# OSO-TIBO-A1-01.net
KiCad netlist of a schematic drawn in EAGLE
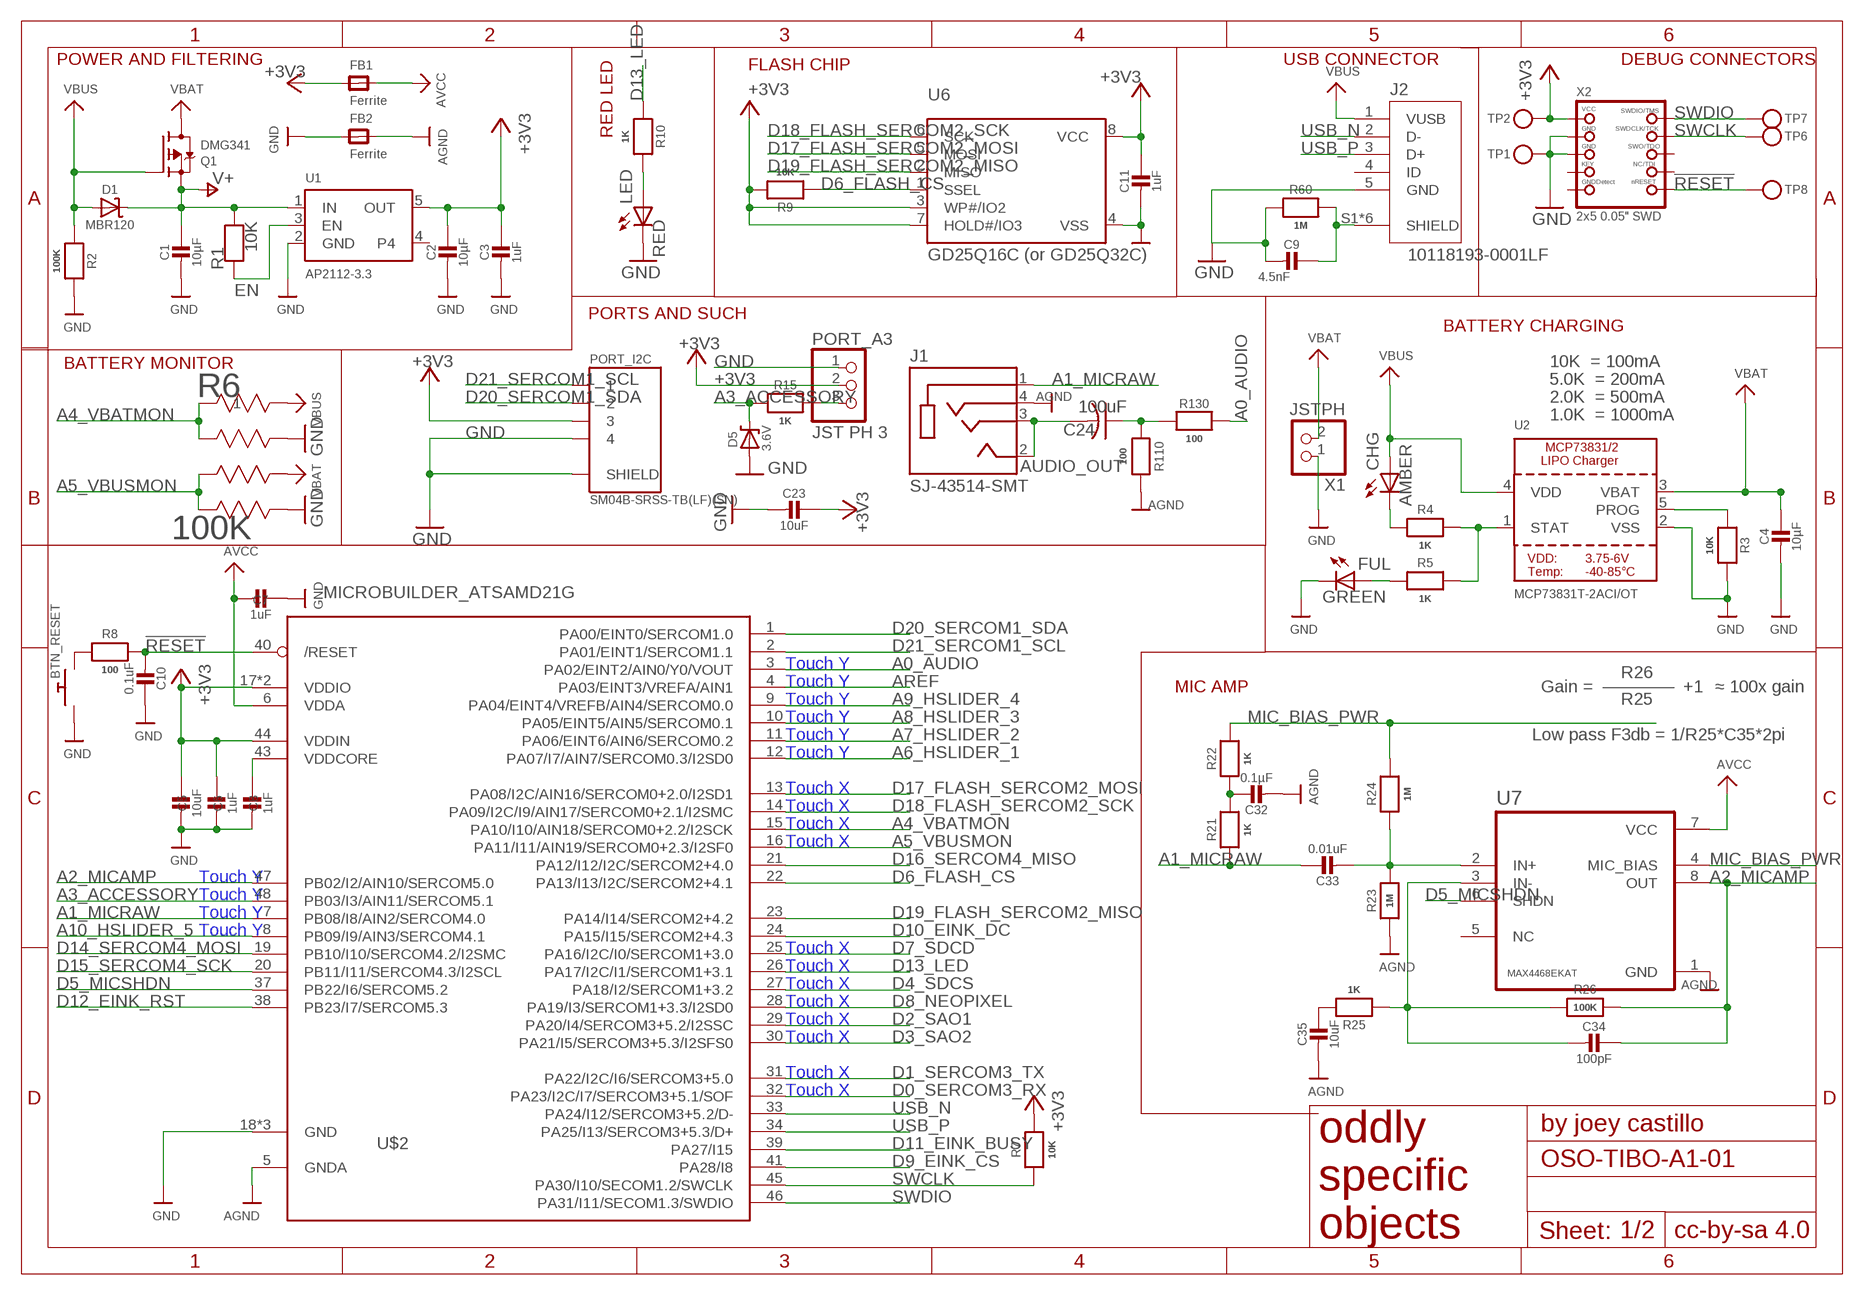
[diagram p0: schematic, sheet 1]
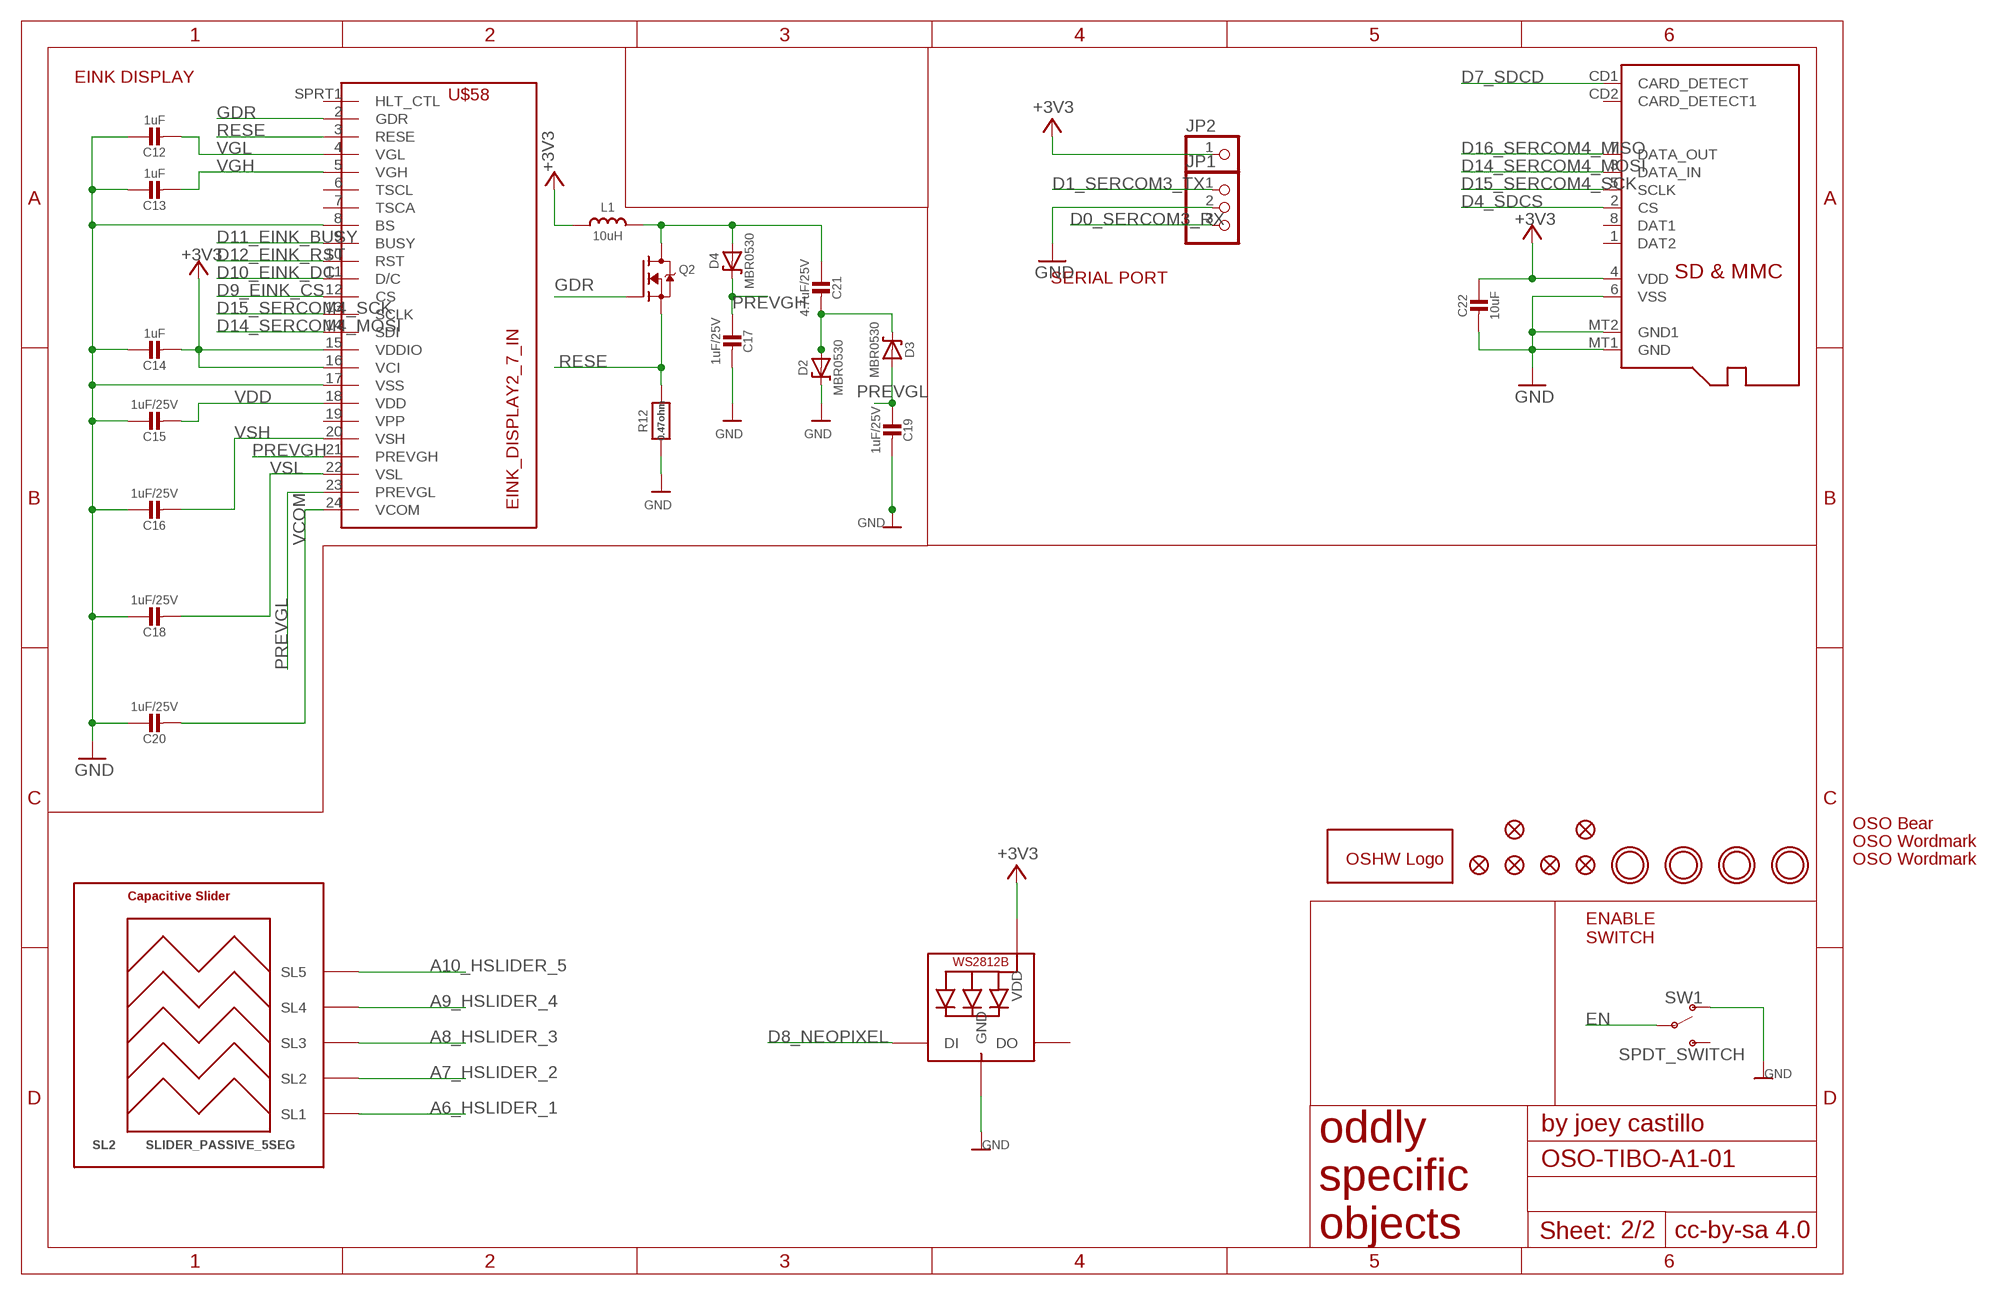
[diagram p1: schematic, sheet 2]

(export (version "E")
  (design (tool "Eeschema 10.0.6"))
  (components
    (comp (ref "BTN_RESET")
      (value "SPST_TACTILE_SWITCHRA-THRU")
      (footprint "eagle-import:MJTP1117")
      (libsource (lib "eagle-import") (part "SPST_TACTILE_SWITCHRA-THRU"))
    )
    (comp (ref "C1")
      (value "10µF")
      (footprint "eagle-import:0805-NO")
      (libsource (lib "eagle-import") (part "CAP_CERAMIC0805-NOOUTLINE"))
    )
    (comp (ref "C2")
      (value "10µF")
      (footprint "eagle-import:0805-NO")
      (libsource (lib "eagle-import") (part "CAP_CERAMIC0805-NOOUTLINE"))
    )
    (comp (ref "C3")
      (value "1uF")
      (footprint "eagle-import:0805-NO")
      (libsource (lib "eagle-import") (part "CAP_CERAMIC0805-NOOUTLINE"))
    )
    (comp (ref "C4")
      (value "10µF")
      (footprint "eagle-import:0805-NO")
      (libsource (lib "eagle-import") (part "CAP_CERAMIC0805-NOOUTLINE"))
    )
    (comp (ref "C5")
      (value "10uF")
      (footprint "eagle-import:0805_10MGAP")
      (libsource (lib "eagle-import") (part "CAP_CERAMIC0805_10MGAP"))
    )
    (comp (ref "C6")
      (value "1uF")
      (footprint "eagle-import:0805-NO")
      (libsource (lib "eagle-import") (part "CAP_CERAMIC0805-NOOUTLINE"))
    )
    (comp (ref "C7")
      (value "1uF")
      (footprint "eagle-import:0805-NO")
      (libsource (lib "eagle-import") (part "CAP_CERAMIC0805-NOOUTLINE"))
    )
    (comp (ref "C8")
      (value "1uF")
      (footprint "eagle-import:0805-NO")
      (libsource (lib "eagle-import") (part "CAP_CERAMIC0805-NOOUTLINE"))
    )
    (comp (ref "C9")
      (value "4.5nF")
      (footprint "eagle-import:0805-NO")
      (libsource (lib "eagle-import") (part "CAP_CERAMIC0805-NOOUTLINE"))
    )
    (comp (ref "C10")
      (value "0.1uF")
      (footprint "eagle-import:0805_10MGAP")
      (libsource (lib "eagle-import") (part "CAP_CERAMIC0805_10MGAP"))
    )
    (comp (ref "C11")
      (value "1uF")
      (footprint "eagle-import:0805_10MGAP")
      (libsource (lib "eagle-import") (part "CAP_CERAMIC0805_10MGAP"))
    )
    (comp (ref "C23")
      (value "10uF")
      (footprint "eagle-import:0805-NO")
      (libsource (lib "eagle-import") (part "CAP_CERAMIC0805-NOOUTLINE"))
    )
    (comp (ref "C24")
      (value "100uF")
      (footprint "eagle-import:C1210")
      (libsource (lib "eagle-import") (part "C-USC1210"))
    )
    (comp (ref "C32")
      (value "0.1µF")
      (footprint "eagle-import:0805-NO")
      (libsource (lib "eagle-import") (part "CAP_CERAMIC0805-NOOUTLINE"))
    )
    (comp (ref "C33")
      (value "0.01uF")
      (footprint "eagle-import:0805-NO")
      (libsource (lib "eagle-import") (part "CAP_CERAMIC0805-NOOUTLINE"))
    )
    (comp (ref "C34")
      (value "100pF")
      (footprint "eagle-import:0805-NO")
      (libsource (lib "eagle-import") (part "CAP_CERAMIC0805-NOOUTLINE"))
    )
    (comp (ref "C35")
      (value "10uF")
      (footprint "eagle-import:0805-NO")
      (libsource (lib "eagle-import") (part "CAP_CERAMIC0805-NOOUTLINE"))
    )
    (comp (ref "CHG")
      (value "AMBER")
      (footprint "eagle-import:CHIP-LED0805")
      (libsource (lib "eagle-import") (part "LEDCHIP-LED0805"))
    )
    (comp (ref "D1")
      (value "MBR120")
      (footprint "eagle-import:SOD-123")
      (libsource (lib "eagle-import") (part "DIODE-SCHOTTKYSOD-123"))
    )
    (comp (ref "D5")
      (value "3.6V")
      (footprint "eagle-import:SOD-123")
      (libsource (lib "eagle-import") (part "DIODE-ZENERSOD123"))
    )
    (comp (ref "FB1")
      (value "Ferrite")
      (footprint "eagle-import:0805")
      (libsource (lib "eagle-import") (part "FERRITE0805"))
    )
    (comp (ref "FB2")
      (value "Ferrite")
      (footprint "eagle-import:0805")
      (libsource (lib "eagle-import") (part "FERRITE0805"))
    )
    (comp (ref "FUL")
      (value "GREEN")
      (footprint "eagle-import:CHIP-LED0805")
      (libsource (lib "eagle-import") (part "LEDCHIP-LED0805"))
    )
    (comp (ref "J1")
      (value "SJ-43514-SMT")
      (footprint "eagle-import:CUI_SJ-43514-SMT")
      (fields
        (field (name "DIGI-KEY_PART_NUMBER") "CP-43514SJCT-ND")
        (field (name "MF") "CUI Inc.")
        (field (name "MP") "SJ-43514-SMT-TR")
      )
      (libsource (lib "eagle-import") (part "SJ-43514-SMT"))
    )
    (comp (ref "J2")
      (value "10118193-0001LF")
      (footprint "eagle-import:FCI_10118193-0001LF")
      (fields (field (name "DIGI-KEY_PART_NUMBER") "609-4616-1-ND") (field (name "MF") "Amphenol ICC"))
      (libsource (lib "eagle-import") (part "10118193-0001LF"))
    )
    (comp (ref "LED")
      (value "RED")
      (footprint "eagle-import:CHIP-LED0805")
      (libsource (lib "eagle-import") (part "LEDCHIP-LED0805"))
    )
    (comp (ref "PORT_A3")
      (value "JST PH 3")
      (footprint "eagle-import:JSTPH3")
      (libsource (lib "eagle-import") (part "CON_JST_PH_3PIN"))
    )
    (comp (ref "PORT_I2C")
      (value "SM04B-SRSS-TB(LF)(SN)")
      (footprint "eagle-import:JST_SM04B-SRSS-TB(LF)(SN)")
      (fields
        (field (name "DIGI-KEY_PART_NUMBER") "455-1804-1-ND")
        (field (name "MF") "JST Sales")
        (field (name "MP") "SM04B-SRSS-TB_LF__SN_")
      )
      (libsource (lib "eagle-import") (part "SM04B-SRSS-TB(LF)(SN)"))
    )
    (comp (ref "Q1")
      (value "DMG341")
      (footprint "eagle-import:SOT23-R")
      (libsource (lib "eagle-import") (part "MOSFET-P"))
    )
    (comp (ref "R1")
      (value "10K")
      (footprint "eagle-import:0805-NO")
      (libsource (lib "eagle-import") (part "RESISTOR0805_NOOUTLINE"))
    )
    (comp (ref "R2")
      (value "100K")
      (footprint "eagle-import:0805-NO")
      (libsource (lib "eagle-import") (part "RESISTOR0805_NOOUTLINE"))
    )
    (comp (ref "R3")
      (value "10K")
      (footprint "eagle-import:0805-NO")
      (libsource (lib "eagle-import") (part "RESISTOR0805_NOOUTLINE"))
    )
    (comp (ref "R4")
      (value "1K")
      (footprint "eagle-import:0805-NO")
      (libsource (lib "eagle-import") (part "RESISTOR0805_NOOUTLINE"))
    )
    (comp (ref "R5")
      (value "1K")
      (footprint "eagle-import:0805-NO")
      (libsource (lib "eagle-import") (part "RESISTOR0805_NOOUTLINE"))
    )
    (comp (ref "R6")
      (value "100K")
      (footprint "eagle-import:EXBV8V")
      (fields (field (name "MANUFACTURER_PART_NUMBER") "EXBV8V103JV"))
      (libsource (lib "eagle-import") (part "EXB-V8V103JV"))
    )
    (comp (ref "R7")
      (value "10K")
      (footprint "eagle-import:0805-NO")
      (libsource (lib "eagle-import") (part "RESISTOR0805_NOOUTLINE"))
    )
    (comp (ref "R8")
      (value "100")
      (footprint "eagle-import:0805_10MGAP")
      (libsource (lib "eagle-import") (part "RESISTOR0805_10MGAP"))
    )
    (comp (ref "R9")
      (value "10K")
      (footprint "eagle-import:0805-NO")
      (libsource (lib "eagle-import") (part "RESISTOR0805_NOOUTLINE"))
    )
    (comp (ref "R10")
      (value "1K")
      (footprint "eagle-import:0805-NO")
      (libsource (lib "eagle-import") (part "RESISTOR0805_NOOUTLINE"))
    )
    (comp (ref "R15")
      (value "1K")
      (footprint "eagle-import:_0805MP")
      (libsource (lib "eagle-import") (part "RESISTOR_0805MP"))
    )
    (comp (ref "R21")
      (value "1K")
      (footprint "eagle-import:0805-NO")
      (libsource (lib "eagle-import") (part "RESISTOR0805_NOOUTLINE"))
    )
    (comp (ref "R22")
      (value "1K")
      (footprint "eagle-import:0805-NO")
      (libsource (lib "eagle-import") (part "RESISTOR0805_NOOUTLINE"))
    )
    (comp (ref "R23")
      (value "1M")
      (footprint "eagle-import:0805-NO")
      (libsource (lib "eagle-import") (part "RESISTOR0805_NOOUTLINE"))
    )
    (comp (ref "R24")
      (value "1M")
      (footprint "eagle-import:0805-NO")
      (libsource (lib "eagle-import") (part "RESISTOR0805_NOOUTLINE"))
    )
    (comp (ref "R25")
      (value "1K")
      (footprint "eagle-import:0805-NO")
      (libsource (lib "eagle-import") (part "RESISTOR0805_NOOUTLINE"))
    )
    (comp (ref "R26")
      (value "100K")
      (footprint "eagle-import:0805-NO")
      (libsource (lib "eagle-import") (part "RESISTOR0805_NOOUTLINE"))
    )
    (comp (ref "R60")
      (value "1M")
      (footprint "eagle-import:0805-NO")
      (libsource (lib "eagle-import") (part "RESISTOR0805_NOOUTLINE"))
    )
    (comp (ref "R110")
      (value "100")
      (footprint "eagle-import:0805-NO")
      (libsource (lib "eagle-import") (part "RESISTOR0805_NOOUTLINE"))
    )
    (comp (ref "R130")
      (value "100")
      (footprint "eagle-import:0805-NO")
      (libsource (lib "eagle-import") (part "RESISTOR0805_NOOUTLINE"))
    )
    (comp (ref "TP1")
      (value "TESTPOINTROUND2MMNO")
      (footprint "eagle-import:TESTPOINT_ROUND_2MM_NO")
      (libsource (lib "eagle-import") (part "TESTPOINTROUND2MMNO"))
    )
    (comp (ref "TP2")
      (value "TESTPOINTROUND2MMNO")
      (footprint "eagle-import:TESTPOINT_ROUND_2MM_NO")
      (libsource (lib "eagle-import") (part "TESTPOINTROUND2MMNO"))
    )
    (comp (ref "TP6")
      (value "TESTPOINTROUND2MMNO")
      (footprint "eagle-import:TESTPOINT_ROUND_2MM_NO")
      (libsource (lib "eagle-import") (part "TESTPOINTROUND2MMNO"))
    )
    (comp (ref "TP7")
      (value "TESTPOINTROUND2MMNO")
      (footprint "eagle-import:TESTPOINT_ROUND_2MM_NO")
      (libsource (lib "eagle-import") (part "TESTPOINTROUND2MMNO"))
    )
    (comp (ref "TP8")
      (value "TESTPOINTROUND2MMNO")
      (footprint "eagle-import:TESTPOINT_ROUND_2MM_NO")
      (libsource (lib "eagle-import") (part "TESTPOINTROUND2MMNO"))
    )
    (comp (ref "U$2")
      (value "MICROBUILDER_ATSAMD21G")
      (footprint "eagle-import:QFP50P900X900X120-48N")
      (libsource (lib "eagle-import") (part "MICROBUILDER_ATSAMD21G"))
    )
    (comp (ref "U1")
      (value "AP2112-3.3")
      (footprint "eagle-import:SOT23-5")
      (libsource (lib "eagle-import") (part "VREG_SOT23-5"))
    )
    (comp (ref "U2")
      (value "MCP73831T-2ACI/OT")
      (footprint "eagle-import:SOT23-5")
      (libsource (lib "eagle-import") (part "MCP73831/2"))
    )
    (comp (ref "U6")
      (value "GD25Q16C (or GD25Q32C)")
      (footprint "eagle-import:MICROBUILDER_SOIC8_150MIL")
      (libsource (lib "eagle-import") (part "MICROBUILDER_SPIFLASH_SOIC8"))
    )
    (comp (ref "U7")
      (value "MAX4468EKAT")
      (footprint "eagle-import:SOT65P280X145-8N")
      (fields
        (field (name "DIGI-KEY_PART_NUMBER") "MAX4468EKA+CT-ND")
        (field (name "MF") "Maxim Integrated")
        (field (name "MP") "MAX4468EKA+T")
      )
      (libsource (lib "eagle-import") (part "MAX4468EKAT"))
    )
    (comp (ref "X1")
      (value "JSTPH")
      (footprint "eagle-import:JSTPH2")
      (libsource (lib "eagle-import") (part "CON_JST_PH_2PIN"))
    )
    (comp (ref "X2")
      (value "2x5 0.05\" SWD")
      (footprint "eagle-import:2X05_1.27MM_BOX_POSTS")
      (libsource (lib "eagle-import") (part "JTAG-CORTEXBOXPOSTS"))
    )
    (comp (ref "C12")
      (value "1uF")
      (footprint "eagle-import:0805_10MGAP")
      (libsource (lib "eagle-import") (part "CAP_CERAMIC0805_10MGAP"))
    )
    (comp (ref "C13")
      (value "1uF")
      (footprint "eagle-import:0805_10MGAP")
      (libsource (lib "eagle-import") (part "CAP_CERAMIC0805_10MGAP"))
    )
    (comp (ref "C14")
      (value "1uF")
      (footprint "eagle-import:0805_10MGAP")
      (libsource (lib "eagle-import") (part "CAP_CERAMIC0805_10MGAP"))
    )
    (comp (ref "C15")
      (value "1uF/25V")
      (footprint "eagle-import:0805_10MGAP")
      (libsource (lib "eagle-import") (part "CAP_CERAMIC0805_10MGAP"))
    )
    (comp (ref "C16")
      (value "1uF/25V")
      (footprint "eagle-import:0805_10MGAP")
      (libsource (lib "eagle-import") (part "CAP_CERAMIC0805_10MGAP"))
    )
    (comp (ref "C17")
      (value "1uF/25V")
      (footprint "eagle-import:0805_10MGAP")
      (libsource (lib "eagle-import") (part "CAP_CERAMIC0805_10MGAP"))
    )
    (comp (ref "C18")
      (value "1uF/25V")
      (footprint "eagle-import:0805_10MGAP")
      (libsource (lib "eagle-import") (part "CAP_CERAMIC0805_10MGAP"))
    )
    (comp (ref "C19")
      (value "1uF/25V")
      (footprint "eagle-import:0805_10MGAP")
      (libsource (lib "eagle-import") (part "CAP_CERAMIC0805_10MGAP"))
    )
    (comp (ref "C20")
      (value "1uF/25V")
      (footprint "eagle-import:0805_10MGAP")
      (libsource (lib "eagle-import") (part "CAP_CERAMIC0805_10MGAP"))
    )
    (comp (ref "C21")
      (value "4.7uF/25V")
      (footprint "eagle-import:0805-NO")
      (libsource (lib "eagle-import") (part "CAP_CERAMIC0805-NOOUTLINE"))
    )
    (comp (ref "C22")
      (value "10uF")
      (footprint "eagle-import:0805_10MGAP")
      (libsource (lib "eagle-import") (part "CAP_CERAMIC0805_10MGAP"))
    )
    (comp (ref "D2")
      (value "MBR0530")
      (footprint "eagle-import:SOD-123")
      (libsource (lib "eagle-import") (part "DIODE-SCHOTTKYSOD-123"))
    )
    (comp (ref "D3")
      (value "MBR0530")
      (footprint "eagle-import:SOD-123")
      (libsource (lib "eagle-import") (part "DIODE-SCHOTTKYSOD-123"))
    )
    (comp (ref "D4")
      (value "MBR0530")
      (footprint "eagle-import:SOD-123")
      (libsource (lib "eagle-import") (part "DIODE-SCHOTTKYSOD-123"))
    )
    (comp (ref "D8_NEOPIXEL")
      (value "WS2812B_4020")
      (footprint "eagle-import:WS2812B_4020")
      (libsource (lib "eagle-import") (part "WS2812B_4020"))
    )
    (comp (ref "FID1")
      (value "FIDUCIAL_1MM")
      (footprint "eagle-import:FIDUCIAL_1MM")
      (libsource (lib "eagle-import") (part "FIDUCIAL_1MM"))
    )
    (comp (ref "FID2")
      (value "FIDUCIAL_1MM")
      (footprint "eagle-import:FIDUCIAL_1MM")
      (libsource (lib "eagle-import") (part "FIDUCIAL_1MM"))
    )
    (comp (ref "FID3")
      (value "FIDUCIAL_1MM")
      (footprint "eagle-import:FIDUCIAL_1MM")
      (libsource (lib "eagle-import") (part "FIDUCIAL_1MM"))
    )
    (comp (ref "FID4")
      (value "FIDUCIAL_1MM")
      (footprint "eagle-import:FIDUCIAL_1MM")
      (libsource (lib "eagle-import") (part "FIDUCIAL_1MM"))
    )
    (comp (ref "FID5")
      (value "FIDUCIAL_1MM")
      (footprint "eagle-import:FIDUCIAL_1MM")
      (libsource (lib "eagle-import") (part "FIDUCIAL_1MM"))
    )
    (comp (ref "FID6")
      (value "FIDUCIAL_1MM")
      (footprint "eagle-import:FIDUCIAL_1MM")
      (libsource (lib "eagle-import") (part "FIDUCIAL_1MM"))
    )
    (comp (ref "GOLD_ORB_SM1")
      (value "OSHWLOGOLOGO5MM")
      (footprint "eagle-import:OSHW_5MM")
      (libsource (lib "eagle-import") (part "OSHWLOGOLOGO5MM"))
    )
    (comp (ref "JP1")
      (value "PINHD-1X3")
      (footprint "eagle-import:1X03")
      (libsource (lib "eagle-import") (part "PINHD-1X3"))
    )
    (comp (ref "JP2")
      (value "PINHD-1X1")
      (footprint "eagle-import:1X01")
      (libsource (lib "eagle-import") (part "PINHD-1X1"))
    )
    (comp (ref "L1")
      (value "10uH")
      (footprint "eagle-import:INDUCTOR_4X4MM_NR401")
      (libsource (lib "eagle-import") (part "INDUCTORNR401"))
    )
    (comp (ref "MICROSD")
      (value "MICROSD")
      (footprint "eagle-import:MICROSD")
      (libsource (lib "eagle-import") (part "MICROSD"))
    )
    (comp (ref "Q2")
      (value "IRLML0100")
      (footprint "eagle-import:SOT23-3")
      (libsource (lib "eagle-import") (part "IRLML2060TRPBF"))
    )
    (comp (ref "R12")
      (value "0.47ohm")
      (footprint "eagle-import:0805_10MGAP")
      (libsource (lib "eagle-import") (part "RESISTOR0805_10MGAP"))
    )
    (comp (ref "SL2")
      (value "SLIDER_PASSIVE_5SEG")
      (footprint "eagle-import:SLIDER_PASSIVE_5SEG_12MM")
      (libsource (lib "eagle-import") (part "SLIDER_PASSIVE_5SEG"))
    )
    (comp (ref "SW1")
      (value "SPDT_SWITCH")
      (footprint "eagle-import:A10767")
      (libsource (lib "eagle-import") (part "SPDT_SWITCH"))
    )
    (comp (ref "U$1")
      (value "MOUNTINGHOLE2.5")
      (footprint "eagle-import:MOUNTINGHOLE_2.5_PLATED")
      (libsource (lib "eagle-import") (part "MOUNTINGHOLE2.5"))
    )
    (comp (ref "U$4")
      (value "MOUNTINGHOLE2.5")
      (footprint "eagle-import:MOUNTINGHOLE_2.5_PLATED")
      (libsource (lib "eagle-import") (part "MOUNTINGHOLE2.5"))
    )
    (comp (ref "U$5")
      (value "MOUNTINGHOLE2.5")
      (footprint "eagle-import:MOUNTINGHOLE_2.5_PLATED")
      (libsource (lib "eagle-import") (part "MOUNTINGHOLE2.5"))
    )
    (comp (ref "U$7")
      (value "MOUNTINGHOLE2.5")
      (footprint "eagle-import:MOUNTINGHOLE_2.5_PLATED")
      (libsource (lib "eagle-import") (part "MOUNTINGHOLE2.5"))
    )
    (comp (ref "U$45")
      (value "OSO_BEAR")
      (footprint "eagle-import:OSO_BEAR_750MIL")
      (libsource (lib "eagle-import") (part "OSO_BEAR"))
    )
    (comp (ref "U$47")
      (value "OSO_TEXT")
      (footprint "eagle-import:OSO_TEXT_435MIL")
      (libsource (lib "eagle-import") (part "OSO_TEXT"))
    )
    (comp (ref "U$48")
      (value "OSO_TEXTOSO_TEXT_ONELINE_125MIL")
      (footprint "eagle-import:OSO_ONELINE_125MIL")
      (libsource (lib "eagle-import") (part "OSO_TEXTOSO_TEXT_ONELINE_125MIL"))
    )
    (comp (ref "U$58")
      (value "EINK_DISPLAY2_7_IN")
      (footprint "eagle-import:EINK_DISPLAY_2_7_IN")
      (libsource (lib "eagle-import") (part "EINK_DISPLAY2_7_IN"))
    )
  )
  (nets
    (net (code "1") (name "+3V3") (class "Default")
      (node (ref "C11") (pin "1") (pinfunction "1_1") (pintype "passive"))
      (node (ref "C14") (pin "2") (pinfunction "2_2") (pintype "passive"))
      (node (ref "C2") (pin "1") (pinfunction "1_1") (pintype "passive"))
      (node (ref "C22") (pin "1") (pinfunction "1_1") (pintype "passive"))
      (node (ref "C23") (pin "1") (pinfunction "1_1") (pintype "passive"))
      (node (ref "C3") (pin "1") (pinfunction "1_1") (pintype "passive"))
      (node (ref "C5") (pin "1") (pinfunction "1_1") (pintype "passive"))
      (node (ref "C6") (pin "1") (pinfunction "1_1") (pintype "passive"))
      (node (ref "D8_NEOPIXEL") (pin "2") (pinfunction "VDD_2") (pintype "power_in"))
      (node (ref "FB1") (pin "1") (pinfunction "P$1_1") (pintype "passive"))
      (node (ref "JP2") (pin "1") (pinfunction "1_1") (pintype "passive"))
      (node (ref "L1") (pin "P$2") (pinfunction "2_P$2") (pintype "passive"))
      (node (ref "MICROSD") (pin "4") (pinfunction "VDD_4") (pintype "power_in"))
      (node (ref "PORT_A3") (pin "2") (pinfunction "2_2") (pintype "passive"))
      (node (ref "PORT_I2C") (pin "3") (pinfunction "3_3") (pintype "passive"))
      (node (ref "R7") (pin "2") (pinfunction "2_2") (pintype "passive"))
      (node (ref "R9") (pin "2") (pinfunction "2_2") (pintype "passive"))
      (node (ref "TP2") (pin "P$1") (pinfunction "P$1_P$1") (pintype "bidirectional"))
      (node (ref "U$2") (pin "17") (pinfunction "VDDIO_17") (pintype "power_in"))
      (node (ref "U$2") (pin "36") (pinfunction "VDDIO_36") (pintype "power_in"))
      (node (ref "U$2") (pin "44") (pinfunction "VDDIN_44") (pintype "power_in"))
      (node (ref "U$58") (pin "15") (pinfunction "VDDIO_15") (pintype "bidirectional"))
      (node (ref "U$58") (pin "16") (pinfunction "VCI_16") (pintype "bidirectional"))
      (node (ref "U1") (pin "5") (pinfunction "OUT_5") (pintype "power_in"))
      (node (ref "U6") (pin "3") (pinfunction "WP#/IO2_3") (pintype "bidirectional"))
      (node (ref "U6") (pin "7") (pinfunction "HOLD#/IO3_7") (pintype "bidirectional"))
      (node (ref "U6") (pin "8") (pinfunction "VCC_8") (pintype "bidirectional"))
      (node (ref "X2") (pin "1") (pinfunction "VCC_1") (pintype "power_in"))
    )
    (net (code "2") (name "A0_AUDIO") (class "Default")
      (node (ref "R130") (pin "1") (pinfunction "1_1") (pintype "passive"))
      (node (ref "U$2") (pin "3") (pinfunction "PA02/EINT2/AIN0/Y0/VOUT_3") (pintype "bidirectional"))
    )
    (net (code "3") (name "A1_MICRAW") (class "Default")
      (node (ref "C33") (pin "1") (pinfunction "1_1") (pintype "passive"))
      (node (ref "J1") (pin "1") (pinfunction "SLEEVE_1") (pintype "passive"))
      (node (ref "R21") (pin "1") (pinfunction "1_1") (pintype "passive"))
      (node (ref "U$2") (pin "7") (pinfunction "PB08/I8/AIN2/SERCOM4.0_7") (pintype "bidirectional"))
    )
    (net (code "4") (name "A2_MICAMP") (class "Default")
      (node (ref "C34") (pin "1") (pinfunction "1_1") (pintype "passive"))
      (node (ref "R26") (pin "2") (pinfunction "2_2") (pintype "passive"))
      (node (ref "U$2") (pin "47") (pinfunction "PB02/I2/AIN10/SERCOM5.0_47") (pintype "bidirectional"))
      (node (ref "U7") (pin "8") (pinfunction "OUT_8") (pintype "output"))
    )
    (net (code "5") (name "A3_ACCESSORY") (class "Default")
      (node (ref "D5") (pin "C") (pinfunction "C_C") (pintype "passive"))
      (node (ref "R15") (pin "2") (pinfunction "2_2") (pintype "passive"))
      (node (ref "U$2") (pin "48") (pinfunction "PB03/I3/AIN11/SERCOM5.1_48") (pintype "bidirectional"))
    )
    (net (code "6") (name "A4_VBATMON") (class "Default")
      (node (ref "R6") (pin "1") (pinfunction "1_1") (pintype "passive"))
      (node (ref "R6") (pin "2") (pinfunction "2_2") (pintype "passive"))
      (node (ref "U$2") (pin "15") (pinfunction "PA10/I10/AIN18/SERCOM0+2.2/I2SCK_15") (pintype "bidirectional"))
    )
    (net (code "7") (name "A5_VBUSMON") (class "Default")
      (node (ref "R6") (pin "3") (pinfunction "3_3") (pintype "passive"))
      (node (ref "R6") (pin "4") (pinfunction "4_4") (pintype "passive"))
      (node (ref "U$2") (pin "16") (pinfunction "PA11/I11/AIN19/SERCOM0+2.3/I2SF0_16") (pintype "bidirectional"))
    )
    (net (code "8") (name "A6_HSLIDER_1") (class "Default")
      (node (ref "SL2") (pin "SL1") (pinfunction "SL1_SL1") (pintype "passive"))
      (node (ref "U$2") (pin "12") (pinfunction "PA07/I7/AIN7/SERCOM0.3/I2SD0_12") (pintype "bidirectional"))
    )
    (net (code "9") (name "A7_HSLIDER_2") (class "Default")
      (node (ref "SL2") (pin "SL2") (pinfunction "SL2_SL2") (pintype "passive"))
      (node (ref "U$2") (pin "11") (pinfunction "PA06/EINT6/AIN6/SERCOM0.2_11") (pintype "bidirectional"))
    )
    (net (code "10") (name "A8_HSLIDER_3") (class "Default")
      (node (ref "SL2") (pin "SL3") (pinfunction "SL3_SL3") (pintype "passive"))
      (node (ref "U$2") (pin "10") (pinfunction "PA05/EINT5/AIN5/SERCOM0.1_10") (pintype "bidirectional"))
    )
    (net (code "11") (name "A9_HSLIDER_4") (class "Default")
      (node (ref "SL2") (pin "SL4") (pinfunction "SL4_SL4") (pintype "passive"))
      (node (ref "U$2") (pin "9") (pinfunction "PA04/EINT4/VREFB/AIN4/SERCOM0.0_9") (pintype "bidirectional"))
    )
    (net (code "12") (name "A10_HSLIDER_5") (class "Default")
      (node (ref "SL2") (pin "SL5") (pinfunction "SL5_SL5") (pintype "passive"))
      (node (ref "U$2") (pin "8") (pinfunction "PB09/I9/AIN3/SERCOM4.1_8") (pintype "bidirectional"))
    )
    (net (code "13") (name "AGND") (class "Default")
      (node (ref "C32") (pin "2") (pinfunction "2_2") (pintype "passive"))
      (node (ref "C35") (pin "2") (pinfunction "2_2") (pintype "passive"))
      (node (ref "FB2") (pin "2") (pinfunction "P$2_2") (pintype "passive"))
      (node (ref "J1") (pin "4") (pinfunction "RING2_4") (pintype "passive"))
      (node (ref "R110") (pin "1") (pinfunction "1_1") (pintype "passive"))
      (node (ref "R23") (pin "1") (pinfunction "1_1") (pintype "passive"))
      (node (ref "U$2") (pin "5") (pinfunction "GNDA_5") (pintype "power_in"))
      (node (ref "U7") (pin "1") (pinfunction "GND_1") (pintype "power_in"))
    )
    (net (code "14") (name "AREF") (class "Default")
      (node (ref "U$2") (pin "4") (pinfunction "PA03/EINT3/VREFA/AIN1_4") (pintype "bidirectional"))
    )
    (net (code "15") (name "AUDIO_OUT") (class "Default")
      (node (ref "C24") (pin "2") (pinfunction "2_2") (pintype "passive"))
      (node (ref "J1") (pin "2") (pinfunction "TIP_2") (pintype "passive"))
      (node (ref "J1") (pin "3") (pinfunction "RING1_3") (pintype "passive"))
    )
    (net (code "16") (name "AVCC") (class "Default")
      (node (ref "C7") (pin "2") (pinfunction "2_2") (pintype "passive"))
      (node (ref "FB1") (pin "2") (pinfunction "P$2_2") (pintype "passive"))
      (node (ref "U$2") (pin "6") (pinfunction "VDDA_6") (pintype "power_in"))
      (node (ref "U7") (pin "7") (pinfunction "VCC_7") (pintype "power_in"))
    )
    (net (code "17") (name "D0_SERCOM3_RX") (class "Default")
      (node (ref "JP1") (pin "3") (pinfunction "3_3") (pintype "passive"))
      (node (ref "U$2") (pin "32") (pinfunction "PA23/I2C/I7/SERCOM3+5.1/SOF_32") (pintype "bidirectional"))
    )
    (net (code "18") (name "D1_SERCOM3_TX") (class "Default")
      (node (ref "JP1") (pin "1") (pinfunction "1_1") (pintype "passive"))
      (node (ref "U$2") (pin "31") (pinfunction "PA22/I2C/I6/SERCOM3+5.0_31") (pintype "bidirectional"))
    )
    (net (code "19") (name "D2_SAO1") (class "Default")
      (node (ref "U$2") (pin "29") (pinfunction "PA20/I4/SERCOM3+5.2/I2SSC_29") (pintype "bidirectional"))
    )
    (net (code "20") (name "D3_SAO2") (class "Default")
      (node (ref "U$2") (pin "30") (pinfunction "PA21/I5/SERCOM3+5.3/I2SFS0_30") (pintype "bidirectional"))
    )
    (net (code "21") (name "D4_SDCS") (class "Default")
      (node (ref "MICROSD") (pin "2") (pinfunction "CS_2") (pintype "input"))
      (node (ref "U$2") (pin "27") (pinfunction "PA18/I2/SERCOM1+3.2_27") (pintype "bidirectional"))
    )
    (net (code "22") (name "D5_MICSHDN") (class "Default")
      (node (ref "U$2") (pin "37") (pinfunction "PB22/I6/SERCOM5.2_37") (pintype "bidirectional"))
      (node (ref "U7") (pin "6") (pinfunction "SHDN_6") (pintype "input"))
    )
    (net (code "23") (name "D6_FLASH_CS") (class "Default")
      (node (ref "R9") (pin "1") (pinfunction "1_1") (pintype "passive"))
      (node (ref "U$2") (pin "22") (pinfunction "PA13/I13/I2C/SERCOM2+4.1_22") (pintype "bidirectional"))
      (node (ref "U6") (pin "1") (pinfunction "SSEL_1") (pintype "bidirectional"))
    )
    (net (code "24") (name "D7_SDCD") (class "Default")
      (node (ref "MICROSD") (pin "CD1") (pinfunction "CARD_DETECT_CD1") (pintype "passive"))
      (node (ref "U$2") (pin "25") (pinfunction "PA16/I2C/I0/SERCOM1+3.0_25") (pintype "bidirectional"))
    )
    (net (code "25") (name "D8_NEOPIXEL") (class "Default")
      (node (ref "D8_NEOPIXEL") (pin "1") (pinfunction "DI_1") (pintype "input"))
      (node (ref "U$2") (pin "28") (pinfunction "PA19/I3/SERCOM1+3.3/I2SD0_28") (pintype "bidirectional"))
    )
    (net (code "26") (name "D9_EINK_CS") (class "Default")
      (node (ref "U$2") (pin "41") (pinfunction "PA28/I8_41") (pintype "bidirectional"))
      (node (ref "U$58") (pin "12") (pinfunction "CS_12") (pintype "bidirectional"))
    )
    (net (code "27") (name "D10_EINK_DC") (class "Default")
      (node (ref "U$2") (pin "24") (pinfunction "PA15/I15/SERCOM2+4.3_24") (pintype "bidirectional"))
      (node (ref "U$58") (pin "11") (pinfunction "D/C_11") (pintype "bidirectional"))
    )
    (net (code "28") (name "D11_EINK_BUSY") (class "Default")
      (node (ref "U$2") (pin "39") (pinfunction "PA27/I15_39") (pintype "bidirectional"))
      (node (ref "U$58") (pin "9") (pinfunction "BUSY_9") (pintype "bidirectional"))
    )
    (net (code "29") (name "D12_EINK_RST") (class "Default")
      (node (ref "U$2") (pin "38") (pinfunction "PB23/I7/SERCOM5.3_38") (pintype "bidirectional"))
      (node (ref "U$58") (pin "10") (pinfunction "RST_10") (pintype "bidirectional"))
    )
    (net (code "30") (name "D13_LED") (class "Default")
      (node (ref "R10") (pin "1") (pinfunction "1_1") (pintype "passive"))
      (node (ref "U$2") (pin "26") (pinfunction "PA17/I2C/I1/SERCOM1+3.1_26") (pintype "bidirectional"))
    )
    (net (code "31") (name "D14_SERCOM4_MOSI") (class "Default")
      (node (ref "MICROSD") (pin "3") (pinfunction "DATA_IN_3") (pintype "input"))
      (node (ref "U$2") (pin "19") (pinfunction "PB10/I10/SERCOM4.2/I2SMC_19") (pintype "bidirectional"))
      (node (ref "U$58") (pin "14") (pinfunction "SDI_14") (pintype "bidirectional"))
    )
    (net (code "32") (name "D15_SERCOM4_SCK") (class "Default")
      (node (ref "MICROSD") (pin "5") (pinfunction "SCLK_5") (pintype "input"))
      (node (ref "U$2") (pin "20") (pinfunction "PB11/I11/SERCOM4.3/I2SCL_20") (pintype "bidirectional"))
      (node (ref "U$58") (pin "13") (pinfunction "SCLK_13") (pintype "bidirectional"))
    )
    (net (code "33") (name "D16_SERCOM4_MISO") (class "Default")
      (node (ref "MICROSD") (pin "7") (pinfunction "DATA_OUT_7") (pintype "output"))
      (node (ref "U$2") (pin "21") (pinfunction "PA12/I12/I2C/SERCOM2+4.0_21") (pintype "bidirectional"))
    )
    (net (code "34") (name "D17_FLASH_SERCOM2_MOSI") (class "Default")
      (node (ref "U$2") (pin "13") (pinfunction "PA08/I2C/AIN16/SERCOM0+2.0/I2SD1_13") (pintype "bidirectional"))
      (node (ref "U6") (pin "5") (pinfunction "MOSI_5") (pintype "bidirectional"))
    )
    (net (code "35") (name "D18_FLASH_SERCOM2_SCK") (class "Default")
      (node (ref "U$2") (pin "14") (pinfunction "PA09/I2C/I9/AIN17/SERCOM0+2.1/I2SMC_14") (pintype "bidirectional"))
      (node (ref "U6") (pin "6") (pinfunction "SCK_6") (pintype "bidirectional"))
    )
    (net (code "36") (name "D19_FLASH_SERCOM2_MISO") (class "Default")
      (node (ref "U$2") (pin "23") (pinfunction "PA14/I14/SERCOM2+4.2_23") (pintype "bidirectional"))
      (node (ref "U6") (pin "2") (pinfunction "MISO_2") (pintype "bidirectional"))
    )
    (net (code "37") (name "D20_SERCOM1_SDA") (class "Default")
      (node (ref "PORT_I2C") (pin "2") (pinfunction "2_2") (pintype "passive"))
      (node (ref "U$2") (pin "1") (pinfunction "PA00/EINT0/SERCOM1.0_1") (pintype "bidirectional"))
    )
    (net (code "38") (name "D21_SERCOM1_SCL") (class "Default")
      (node (ref "PORT_I2C") (pin "1") (pinfunction "1_1") (pintype "passive"))
      (node (ref "U$2") (pin "2") (pinfunction "PA01/EINT1/SERCOM1.1_2") (pintype "bidirectional"))
    )
    (net (code "39") (name "EN") (class "Default")
      (node (ref "R1") (pin "1") (pinfunction "1_1") (pintype "passive"))
      (node (ref "SW1") (pin "P$2") (pinfunction "P_P$2") (pintype "passive"))
      (node (ref "U1") (pin "3") (pinfunction "EN_3") (pintype "input"))
    )
    (net (code "40") (name "GDR") (class "Default")
      (node (ref "Q2") (pin "1") (pinfunction "G_1") (pintype "bidirectional"))
      (node (ref "U$58") (pin "2") (pinfunction "GDR_2") (pintype "bidirectional"))
    )
    (net (code "41") (name "GND") (class "Default")
      (node (ref "BTN_RESET") (pin "P$1") (pinfunction "P$1_P$1") (pintype "passive"))
      (node (ref "C1") (pin "2") (pinfunction "2_2") (pintype "passive"))
      (node (ref "C10") (pin "1") (pinfunction "1_1") (pintype "passive"))
      (node (ref "C11") (pin "2") (pinfunction "2_2") (pintype "passive"))
      (node (ref "C12") (pin "1") (pinfunction "1_1") (pintype "passive"))
      (node (ref "C13") (pin "1") (pinfunction "1_1") (pintype "passive"))
      (node (ref "C14") (pin "1") (pinfunction "1_1") (pintype "passive"))
      (node (ref "C15") (pin "1") (pinfunction "1_1") (pintype "passive"))
      (node (ref "C16") (pin "1") (pinfunction "1_1") (pintype "passive"))
      (node (ref "C17") (pin "2") (pinfunction "2_2") (pintype "passive"))
      (node (ref "C18") (pin "1") (pinfunction "1_1") (pintype "passive"))
      (node (ref "C19") (pin "2") (pinfunction "2_2") (pintype "passive"))
      (node (ref "C2") (pin "2") (pinfunction "2_2") (pintype "passive"))
      (node (ref "C20") (pin "1") (pinfunction "1_1") (pintype "passive"))
      (node (ref "C22") (pin "2") (pinfunction "2_2") (pintype "passive"))
      (node (ref "C23") (pin "2") (pinfunction "2_2") (pintype "passive"))
      (node (ref "C3") (pin "2") (pinfunction "2_2") (pintype "passive"))
      (node (ref "C4") (pin "2") (pinfunction "2_2") (pintype "passive"))
      (node (ref "C5") (pin "2") (pinfunction "2_2") (pintype "passive"))
      (node (ref "C6") (pin "2") (pinfunction "2_2") (pintype "passive"))
      (node (ref "C7") (pin "1") (pinfunction "1_1") (pintype "passive"))
      (node (ref "C8") (pin "2") (pinfunction "2_2") (pintype "passive"))
      (node (ref "C9") (pin "2") (pinfunction "2_2") (pintype "passive"))
      (node (ref "D2") (pin "C") (pinfunction "C_C") (pintype "passive"))
      (node (ref "D5") (pin "A") (pinfunction "A_A") (pintype "passive"))
      (node (ref "D8_NEOPIXEL") (pin "4") (pinfunction "GND_4") (pintype "power_in"))
      (node (ref "FB2") (pin "1") (pinfunction "P$1_1") (pintype "passive"))
      (node (ref "FUL") (pin "C") (pinfunction "C_C") (pintype "passive"))
      (node (ref "J2") (pin "5") (pinfunction "GND_5") (pintype "passive"))
      (node (ref "JP1") (pin "2") (pinfunction "2_2") (pintype "passive"))
      (node (ref "LED") (pin "C") (pinfunction "C_C") (pintype "passive"))
      (node (ref "MICROSD") (pin "6") (pinfunction "VSS_6") (pintype "power_in"))
      (node (ref "MICROSD") (pin "MT1") (pinfunction "GND_MT1") (pintype "power_in"))
      (node (ref "MICROSD") (pin "MT2") (pinfunction "GND1_MT2") (pintype "power_in"))
      (node (ref "PORT_A3") (pin "1") (pinfunction "1_1") (pintype "passive"))
      (node (ref "PORT_I2C") (pin "4") (pinfunction "4_4") (pintype "passive"))
      (node (ref "PORT_I2C") (pin "S1") (pinfunction "SHIELD_S1") (pintype "passive"))
      (node (ref "PORT_I2C") (pin "S2") (pinfunction "SHIELD_S2") (pintype "passive"))
      (node (ref "R12") (pin "2") (pinfunction "2_2") (pintype "passive"))
      (node (ref "R2") (pin "2") (pinfunction "2_2") (pintype "passive"))
      (node (ref "R3") (pin "2") (pinfunction "2_2") (pintype "passive"))
      (node (ref "R6") (pin "5") (pinfunction "5_5") (pintype "passive"))
      (node (ref "R6") (pin "7") (pinfunction "7_7") (pintype "passive"))
      (node (ref "R60") (pin "2") (pinfunction "2_2") (pintype "passive"))
      (node (ref "SW1") (pin "P$1") (pinfunction "O_P$1") (pintype "passive"))
      (node (ref "TP1") (pin "P$1") (pinfunction "P$1_P$1") (pintype "bidirectional"))
      (node (ref "U$2") (pin "18") (pinfunction "GND_18") (pintype "power_in"))
      (node (ref "U$2") (pin "35") (pinfunction "GND_35") (pintype "power_in"))
      (node (ref "U$2") (pin "42") (pinfunction "GND_42") (pintype "power_in"))
      (node (ref "U$58") (pin "17") (pinfunction "VSS_17") (pintype "bidirectional"))
      (node (ref "U$58") (pin "8") (pinfunction "BS_8") (pintype "bidirectional"))
      (node (ref "U1") (pin "2") (pinfunction "GND_2") (pintype "power_in"))
      (node (ref "U2") (pin "2") (pinfunction "VSS_2") (pintype "power_in"))
      (node (ref "U6") (pin "4") (pinfunction "VSS_4") (pintype "bidirectional"))
      (node (ref "X1") (pin "1") (pinfunction "1_1") (pintype "passive"))
      (node (ref "X2") (pin "3") (pinfunction "GND_3") (pintype "power_in"))
      (node (ref "X2") (pin "5") (pinfunction "GND_5") (pintype "power_in"))
    )
    (net (code "42") (name "MIC_BIAS_PWR") (class "Default")
      (node (ref "R22") (pin "2") (pinfunction "2_2") (pintype "passive"))
      (node (ref "R24") (pin "2") (pinfunction "2_2") (pintype "passive"))
      (node (ref "U7") (pin "4") (pinfunction "MIC_BIAS_4") (pintype "output"))
    )
    (net (code "43") (name "Net-(BTN_RESET-PadP$2)") (class "Default")
      (node (ref "BTN_RESET") (pin "P$2") (pinfunction "P$2_P$2") (pintype "passive"))
      (node (ref "R8") (pin "1") (pinfunction "1_1") (pintype "passive"))
    )
    (net (code "44") (name "Net-(C9-Pad1)") (class "Default")
      (node (ref "C9") (pin "1") (pinfunction "1_1") (pintype "passive"))
      (node (ref "J2") (pin "S1") (pinfunction "SHIELD_S1") (pintype "passive"))
      (node (ref "J2") (pin "S2") (pinfunction "SHIELD_S2") (pintype "passive"))
      (node (ref "J2") (pin "S3") (pinfunction "SHIELD_S3") (pintype "passive"))
      (node (ref "J2") (pin "S4") (pinfunction "SHIELD_S4") (pintype "passive"))
      (node (ref "J2") (pin "S5") (pinfunction "SHIELD_S5") (pintype "passive"))
      (node (ref "J2") (pin "S6") (pinfunction "SHIELD_S6") (pintype "passive"))
      (node (ref "R60") (pin "1") (pinfunction "1_1") (pintype "passive"))
    )
    (net (code "45") (name "Net-(C21-Pad2)") (class "Default")
      (node (ref "C21") (pin "2") (pinfunction "2_2") (pintype "passive"))
      (node (ref "D2") (pin "A") (pinfunction "A_A") (pintype "passive"))
      (node (ref "D3") (pin "C") (pinfunction "C_C") (pintype "passive"))
    )
    (net (code "46") (name "Net-(C24-Pad1)") (class "Default")
      (node (ref "C24") (pin "1") (pinfunction "1_1") (pintype "passive"))
      (node (ref "R110") (pin "2") (pinfunction "2_2") (pintype "passive"))
      (node (ref "R130") (pin "2") (pinfunction "2_2") (pintype "passive"))
    )
    (net (code "47") (name "Net-(C32-Pad1)") (class "Default")
      (node (ref "C32") (pin "1") (pinfunction "1_1") (pintype "passive"))
      (node (ref "R21") (pin "2") (pinfunction "2_2") (pintype "passive"))
      (node (ref "R22") (pin "1") (pinfunction "1_1") (pintype "passive"))
    )
    (net (code "48") (name "Net-(C35-Pad1)") (class "Default")
      (node (ref "C35") (pin "1") (pinfunction "1_1") (pintype "passive"))
      (node (ref "R25") (pin "2") (pinfunction "2_2") (pintype "passive"))
    )
    (net (code "49") (name "Net-(CHG-PadC)") (class "Default")
      (node (ref "CHG") (pin "C") (pinfunction "C_C") (pintype "passive"))
      (node (ref "R4") (pin "1") (pinfunction "1_1") (pintype "passive"))
    )
    (net (code "50") (name "Net-(FUL-PadA)") (class "Default")
      (node (ref "FUL") (pin "A") (pinfunction "A_A") (pintype "passive"))
      (node (ref "R5") (pin "1") (pinfunction "1_1") (pintype "passive"))
    )
    (net (code "51") (name "Net-(L1-1)") (class "Default")
      (node (ref "C21") (pin "1") (pinfunction "1_1") (pintype "passive"))
      (node (ref "D4") (pin "A") (pinfunction "A_A") (pintype "passive"))
      (node (ref "L1") (pin "P$1") (pinfunction "1_P$1") (pintype "passive"))
      (node (ref "Q2") (pin "3") (pinfunction "D_3") (pintype "bidirectional"))
    )
    (net (code "52") (name "Net-(LED-PadA)") (class "Default")
      (node (ref "LED") (pin "A") (pinfunction "A_A") (pintype "passive"))
      (node (ref "R10") (pin "2") (pinfunction "2_2") (pintype "passive"))
    )
    (net (code "53") (name "Net-(PORT_A3-Pad3)") (class "Default")
      (node (ref "PORT_A3") (pin "3") (pinfunction "3_3") (pintype "passive"))
      (node (ref "R15") (pin "1") (pinfunction "1_1") (pintype "passive"))
    )
    (net (code "54") (name "Net-(U$2-VDDCORE)") (class "Default")
      (node (ref "C8") (pin "1") (pinfunction "1_1") (pintype "passive"))
      (node (ref "U$2") (pin "43") (pinfunction "VDDCORE_43") (pintype "power_in"))
    )
    (net (code "55") (name "Net-(U2-PROG)") (class "Default")
      (node (ref "R3") (pin "1") (pinfunction "1_1") (pintype "passive"))
      (node (ref "U2") (pin "5") (pinfunction "PROG_5") (pintype "input"))
    )
    (net (code "56") (name "Net-(U2-STAT)") (class "Default")
      (node (ref "R4") (pin "2") (pinfunction "2_2") (pintype "passive"))
      (node (ref "R5") (pin "2") (pinfunction "2_2") (pintype "passive"))
      (node (ref "U2") (pin "1") (pinfunction "STAT_1") (pintype "output"))
    )
    (net (code "57") (name "Net-(U7-IN+)") (class "Default")
      (node (ref "C33") (pin "2") (pinfunction "2_2") (pintype "passive"))
      (node (ref "R23") (pin "2") (pinfunction "2_2") (pintype "passive"))
      (node (ref "R24") (pin "1") (pinfunction "1_1") (pintype "passive"))
      (node (ref "U7") (pin "2") (pinfunction "IN+_2") (pintype "input"))
    )
    (net (code "58") (name "Net-(U7-IN-)") (class "Default")
      (node (ref "C34") (pin "2") (pinfunction "2_2") (pintype "passive"))
      (node (ref "R25") (pin "1") (pinfunction "1_1") (pintype "passive"))
      (node (ref "R26") (pin "1") (pinfunction "1_1") (pintype "passive"))
      (node (ref "U7") (pin "3") (pinfunction "IN-_3") (pintype "input"))
    )
    (net (code "59") (name "PREVGH") (class "Default")
      (node (ref "C17") (pin "1") (pinfunction "1_1") (pintype "passive"))
      (node (ref "D4") (pin "C") (pinfunction "C_C") (pintype "passive"))
      (node (ref "U$58") (pin "21") (pinfunction "PREVGH_21") (pintype "bidirectional"))
    )
    (net (code "60") (name "PREVGL") (class "Default")
      (node (ref "C19") (pin "1") (pinfunction "1_1") (pintype "passive"))
      (node (ref "D3") (pin "A") (pinfunction "A_A") (pintype "passive"))
      (node (ref "U$58") (pin "23") (pinfunction "PREVGL_23") (pintype "bidirectional"))
    )
    (net (code "61") (name "RESE") (class "Default")
      (node (ref "Q2") (pin "2") (pinfunction "S_2") (pintype "bidirectional"))
      (node (ref "R12") (pin "1") (pinfunction "1_1") (pintype "passive"))
      (node (ref "U$58") (pin "3") (pinfunction "RESE_3") (pintype "bidirectional"))
    )
    (net (code "62") (name "SWCLK") (class "Default")
      (node (ref "R7") (pin "1") (pinfunction "1_1") (pintype "passive"))
      (node (ref "TP6") (pin "P$1") (pinfunction "P$1_P$1") (pintype "bidirectional"))
      (node (ref "U$2") (pin "45") (pinfunction "PA30/I10/SECOM1.2/SWCLK_45") (pintype "bidirectional"))
      (node (ref "X2") (pin "4") (pinfunction "SWDCLK_4") (pintype "bidirectional"))
    )
    (net (code "63") (name "SWDIO") (class "Default")
      (node (ref "TP7") (pin "P$1") (pinfunction "P$1_P$1") (pintype "bidirectional"))
      (node (ref "U$2") (pin "46") (pinfunction "PA31/I11/SECOM1.3/SWDIO_46") (pintype "bidirectional"))
      (node (ref "X2") (pin "2") (pinfunction "SWDIO_2") (pintype "bidirectional"))
    )
    (net (code "64") (name "USB_N") (class "Default")
      (node (ref "J2") (pin "2") (pinfunction "D-_2") (pintype "passive"))
      (node (ref "U$2") (pin "33") (pinfunction "PA24/I12/SERCOM3+5.2/D-_33") (pintype "bidirectional"))
    )
    (net (code "65") (name "USB_P") (class "Default")
      (node (ref "J2") (pin "3") (pinfunction "D+_3") (pintype "passive"))
      (node (ref "U$2") (pin "34") (pinfunction "PA25/I13/SERCOM3+5.3/D+_34") (pintype "bidirectional"))
    )
    (net (code "66") (name "V+") (class "Default")
      (node (ref "C1") (pin "1") (pinfunction "1_1") (pintype "passive"))
      (node (ref "D1") (pin "C") (pinfunction "C_C") (pintype "passive"))
      (node (ref "Q1") (pin "2") (pinfunction "S_2") (pintype "passive"))
      (node (ref "R1") (pin "2") (pinfunction "2_2") (pintype "passive"))
      (node (ref "U1") (pin "1") (pinfunction "IN_1") (pintype "power_in"))
    )
    (net (code "67") (name "VBAT") (class "Default")
      (node (ref "C4") (pin "1") (pinfunction "1_1") (pintype "passive"))
      (node (ref "Q1") (pin "3") (pinfunction "D_3") (pintype "passive"))
      (node (ref "R6") (pin "6") (pinfunction "6_6") (pintype "passive"))
      (node (ref "U2") (pin "3") (pinfunction "VBAT_3") (pintype "power_in"))
      (node (ref "X1") (pin "2") (pinfunction "2_2") (pintype "passive"))
    )
    (net (code "68") (name "VBUS") (class "Default")
      (node (ref "CHG") (pin "A") (pinfunction "A_A") (pintype "passive"))
      (node (ref "D1") (pin "A") (pinfunction "A_A") (pintype "passive"))
      (node (ref "J2") (pin "1") (pinfunction "VUSB_1") (pintype "passive"))
      (node (ref "Q1") (pin "1") (pinfunction "G_1") (pintype "passive"))
      (node (ref "R2") (pin "1") (pinfunction "1_1") (pintype "passive"))
      (node (ref "R6") (pin "8") (pinfunction "8_8") (pintype "passive"))
      (node (ref "U2") (pin "4") (pinfunction "VDD_4") (pintype "power_in"))
    )
    (net (code "69") (name "VCOM") (class "Default")
      (node (ref "C20") (pin "2") (pinfunction "2_2") (pintype "passive"))
      (node (ref "U$58") (pin "24") (pinfunction "VCOM_24") (pintype "bidirectional"))
    )
    (net (code "70") (name "VDD") (class "Default")
      (node (ref "C15") (pin "2") (pinfunction "2_2") (pintype "passive"))
      (node (ref "U$58") (pin "18") (pinfunction "VDD_18") (pintype "bidirectional"))
    )
    (net (code "71") (name "VGH") (class "Default")
      (node (ref "C13") (pin "2") (pinfunction "2_2") (pintype "passive"))
      (node (ref "U$58") (pin "5") (pinfunction "VGH_5") (pintype "bidirectional"))
    )
    (net (code "72") (name "VGL") (class "Default")
      (node (ref "C12") (pin "2") (pinfunction "2_2") (pintype "passive"))
      (node (ref "U$58") (pin "4") (pinfunction "VGL_4") (pintype "bidirectional"))
    )
    (net (code "73") (name "VSH") (class "Default")
      (node (ref "C16") (pin "2") (pinfunction "2_2") (pintype "passive"))
      (node (ref "U$58") (pin "20") (pinfunction "VSH_20") (pintype "bidirectional"))
    )
    (net (code "74") (name "VSL") (class "Default")
      (node (ref "C18") (pin "2") (pinfunction "2_2") (pintype "passive"))
      (node (ref "U$58") (pin "22") (pinfunction "VSL_22") (pintype "bidirectional"))
    )
    (net (code "75") (name "unconnected-(D8_NEOPIXEL-DO-Pad3)") (class "Default")
      (node (ref "D8_NEOPIXEL") (pin "3") (pinfunction "DO_3") (pintype "output"))
    )
    (net (code "76") (name "unconnected-(J2-ID-Pad4)") (class "Default")
      (node (ref "J2") (pin "4") (pinfunction "ID_4") (pintype "passive"))
    )
    (net (code "77") (name "unconnected-(MICROSD-CARD_DETECT1-PadCD2)") (class "Default")
      (node (ref "MICROSD") (pin "CD2") (pinfunction "CARD_DETECT1_CD2") (pintype "passive"))
    )
    (net (code "78") (name "unconnected-(MICROSD-DAT1-Pad8)") (class "Default")
      (node (ref "MICROSD") (pin "8") (pinfunction "DAT1_8") (pintype "bidirectional"))
    )
    (net (code "79") (name "unconnected-(MICROSD-DAT2-Pad1)") (class "Default")
      (node (ref "MICROSD") (pin "1") (pinfunction "DAT2_1") (pintype "bidirectional"))
    )
    (net (code "80") (name "unconnected-(SW1-S-PadP$3)") (class "Default")
      (node (ref "SW1") (pin "P$3") (pinfunction "S_P$3") (pintype "passive"))
    )
    (net (code "81") (name "unconnected-(U$58-HLT_CTL-PadSPRT1)") (class "Default")
      (node (ref "U$58") (pin "SPRT1") (pinfunction "HLT_CTL_SPRT1") (pintype "bidirectional"))
    )
    (net (code "82") (name "unconnected-(U$58-TSCA-Pad7)") (class "Default")
      (node (ref "U$58") (pin "7") (pinfunction "TSCA_7") (pintype "bidirectional"))
    )
    (net (code "83") (name "unconnected-(U$58-TSCL-Pad6)") (class "Default")
      (node (ref "U$58") (pin "6") (pinfunction "TSCL_6") (pintype "bidirectional"))
    )
    (net (code "84") (name "unconnected-(U$58-VPP-Pad19)") (class "Default")
      (node (ref "U$58") (pin "19") (pinfunction "VPP_19") (pintype "bidirectional"))
    )
    (net (code "85") (name "unconnected-(U1-P4-Pad4)") (class "Default")
      (node (ref "U1") (pin "4") (pinfunction "P4_4") (pintype "bidirectional"))
    )
    (net (code "86") (name "unconnected-(U7-NC-Pad5)") (class "Default")
      (node (ref "U7") (pin "5") (pinfunction "NC_5") (pintype "bidirectional"))
    )
    (net (code "87") (name "unconnected-(X2-GNDDETECT-Pad9)") (class "Default")
      (node (ref "X2") (pin "9") (pinfunction "GNDDETECT_9") (pintype "bidirectional"))
    )
    (net (code "88") (name "unconnected-(X2-KEY-Pad7)") (class "Default")
      (node (ref "X2") (pin "7") (pinfunction "KEY_7") (pintype "bidirectional"))
    )
    (net (code "89") (name "unconnected-(X2-SWO-Pad6)") (class "Default")
      (node (ref "X2") (pin "6") (pinfunction "SWO_6") (pintype "bidirectional"))
    )
    (net (code "90") (name "unconnected-(X2-TDI-Pad8)") (class "Default")
      (node (ref "X2") (pin "8") (pinfunction "TDI_8") (pintype "bidirectional"))
    )
    (net (code "91") (name "~{RESET}") (class "Default")
      (node (ref "C10") (pin "2") (pinfunction "2_2") (pintype "passive"))
      (node (ref "R8") (pin "2") (pinfunction "2_2") (pintype "passive"))
      (node (ref "TP8") (pin "P$1") (pinfunction "P$1_P$1") (pintype "bidirectional"))
      (node (ref "U$2") (pin "40") (pinfunction "/RESET_40") (pintype "bidirectional"))
      (node (ref "X2") (pin "10") (pinfunction "NRESET_10") (pintype "bidirectional"))
    )
  )
)
